# PowerSupply.net
KiCad netlist of a schematic drawn in Altium Designer
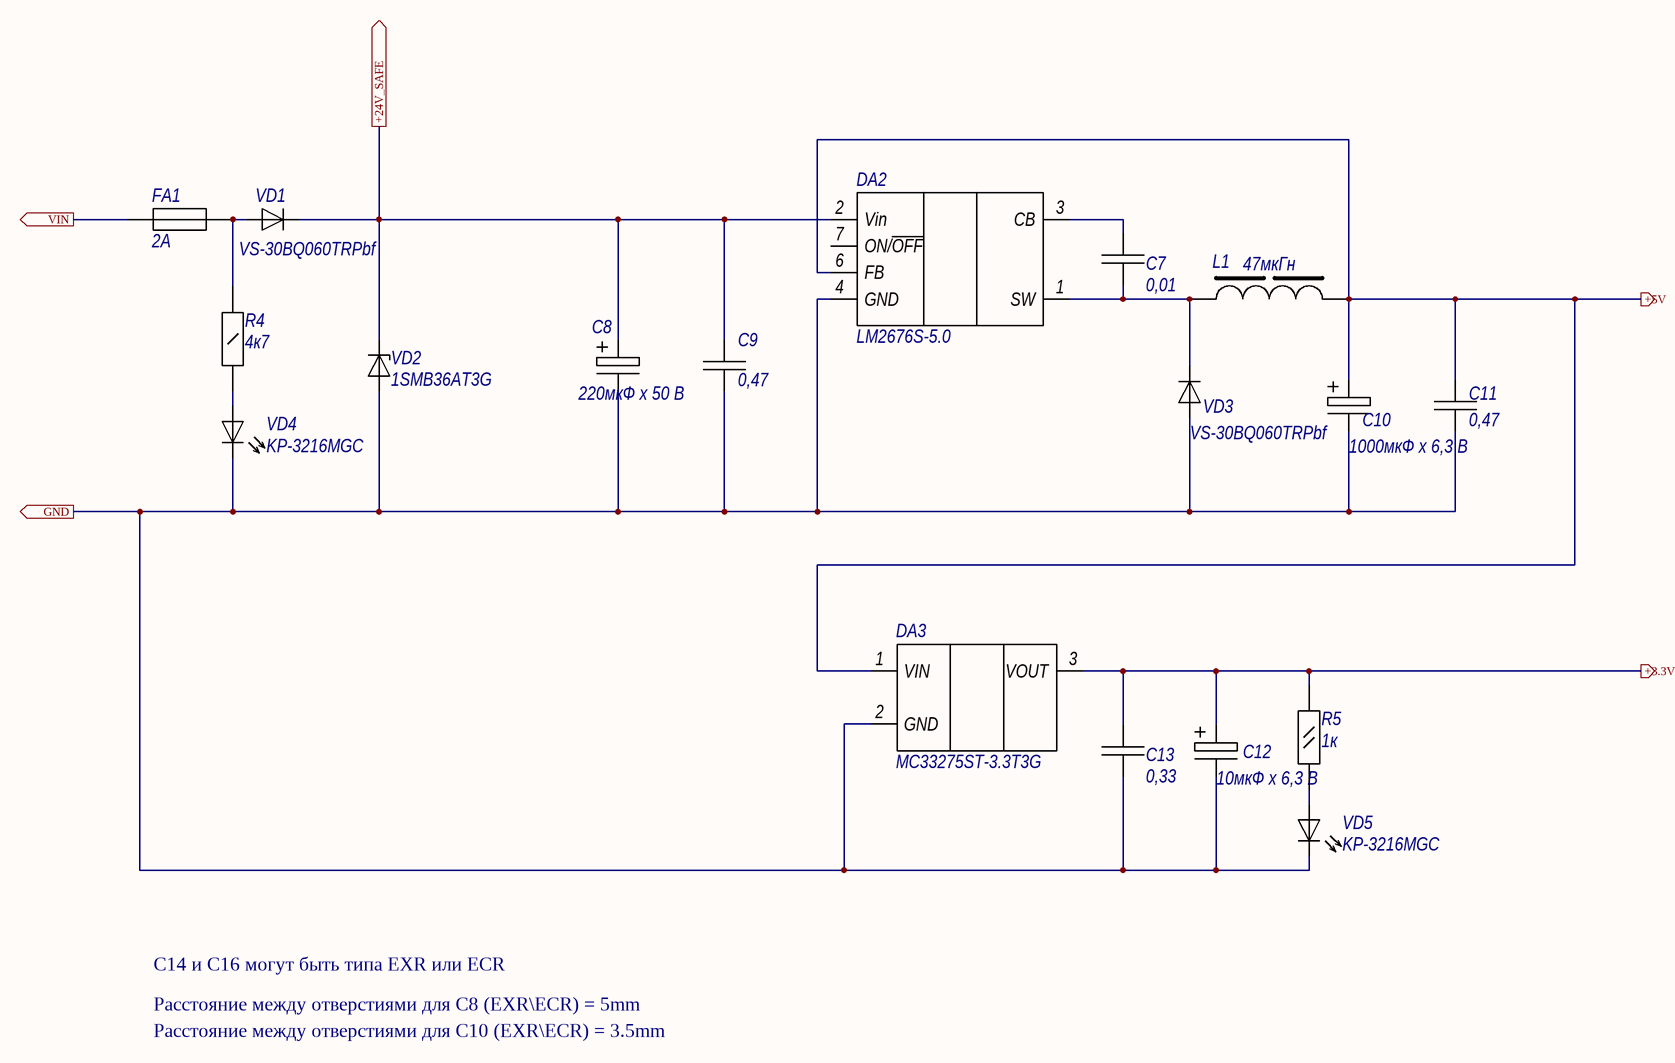
[diagram p0: PowerSupply.SchDoc]

(export (version "E")
  (design (tool "Eeschema 10.0.6"))
  (components
    (comp (ref "C7")
      (value "0,01")
      (footprint "0805")
      (description "Конденсатор")
      (fields (field (name "MANUFACTURER") "YAGEO"))
      (libsource (lib "DX_test_lib2") (part "CC0805"))
    )
    (comp (ref "C8")
      (value "220мкФ x 50 В")
      (footprint "ELCAP_SIZE_F")
      (description "Конденсатор электролитический")
      (fields (field (name "MANUFACTURER") "HITANO"))
      (libsource (lib "DX_test_lib2") (part "EZV-F"))
    )
    (comp (ref "C9")
      (value "0,47")
      (footprint "1206")
      (fields (field (name "MANUFACTURER") "YAGEO"))
      (libsource (lib "Capacitors") (part "CC1206"))
    )
    (comp (ref "C10")
      (value "1000мкФ x 6,3 В")
      (footprint "ELCAP_SIZE_F")
      (description "Конденсатор электролитический")
      (fields (field (name "MANUFACTURER") "HITANO"))
      (libsource (lib "DX_test_lib2") (part "EZV-F"))
    )
    (comp (ref "C11")
      (value "0,47")
      (footprint "1206")
      (fields (field (name "MANUFACTURER") "YAGEO"))
      (libsource (lib "Capacitors") (part "CC1206"))
    )
    (comp (ref "C12")
      (value "10мкФ x 6,3 В")
      (footprint "CAP_TYPE_A")
      (fields (field (name "MANUFACTURER") "Vishay"))
      (libsource (lib "Capacitors") (part "TANTAL_A"))
    )
    (comp (ref "C13")
      (value "0,33")
      (footprint "0805")
      (description "Конденсатор")
      (fields (field (name "MANUFACTURER") "YAGEO"))
      (libsource (lib "DX_test_lib2") (part "CC0805"))
    )
    (comp (ref "DA2")
      (value "LM2676S-5.0")
      (footprint "DDPAK")
      (description "понижающи регулятор 3 А")
      (fields (field (name "MANUFACTURER") "Texas Instr."))
      (libsource (lib "DX_test_lib2") (part "LM2676S"))
    )
    (comp (ref "DA3")
      (value "MC33275ST-3.3T3G")
      (footprint "SOT-223_2")
      (description "Линейный стабилизатор напряжения")
      (fields (field (name "MANUFACTURER") "ON Semi."))
      (libsource (lib "Micro_Analog") (part "MC33275ST"))
    )
    (comp (ref "FA1")
      (value "2А")
      (footprint "RUE-185")
      (description "Предохранитель 3,7 А 30 В")
      (fields (field (name "MANUFACTURER") "Tyco"))
      (libsource (lib "Miscellaneous") (part "RUE-185"))
    )
    (comp (ref "L1")
      (value "47мкГн")
      (footprint "B82464g4")
      (description "Силовой дроссель")
      (fields (field (name "MANUFACTURER") "Epcos"))
      (libsource (lib "DX_test_lib2") (part "B82464g4"))
    )
    (comp (ref "R4")
      (value "4к7")
      (footprint "1206")
      (description "Резистор общего назначения 5%")
      (fields (field (name "MANUFACTURER") "YAGEO"))
      (libsource (lib "Resistors") (part "RC1206JR"))
    )
    (comp (ref "R5")
      (value "1к")
      (footprint "0805")
      (description "Резистор общего назначения 5%")
      (fields (field (name "MANUFACTURER") "YAGEO"))
      (libsource (lib "DX_test_lib2") (part "RC0805JR"))
    )
    (comp (ref "VD1")
      (value "VS-30BQ060TRPbf")
      (footprint "SMC")
      (description "Диод Шотки 60 В 3 А")
      (fields (field (name "MANUFACTURER") "Vishay"))
      (libsource (lib "Diodes") (part "30BQ60"))
    )
    (comp (ref "VD2")
      (value "1SMB36AT3G")
      (footprint "SMB")
      (description "Диод защитный 600 Вт 36 В")
      (fields (field (name "MANUFACTURER") "On Semi."))
      (libsource (lib "Diodes") (part "1SMB36"))
    )
    (comp (ref "VD3")
      (value "VS-30BQ060TRPbf")
      (footprint "SMC")
      (description "Диод Шотки 60 В 3 А")
      (fields (field (name "MANUFACTURER") "Vishay"))
      (libsource (lib "Diodes") (part "30BQ60"))
    )
    (comp (ref "VD4")
      (value "KP-3216MGC")
      (footprint "LED3216")
      (description "Светодиод")
      (fields (field (name "MANUFACTURER") "Kingbright"))
      (libsource (lib "DX_test_lib2") (part "KP-3216"))
    )
    (comp (ref "VD5")
      (value "KP-3216MGC")
      (footprint "LED3216")
      (description "Светодиод")
      (fields (field (name "MANUFACTURER") "Kingbright"))
      (libsource (lib "DX_test_lib2") (part "KP-3216"))
    )
  )
  (nets
    (net (code "1") (name "/+3.3V") (class "Default")
      (node (ref "C12") (pin "1") (pinfunction "1_1") (pintype "passive"))
      (node (ref "C13") (pin "1") (pinfunction "1_1") (pintype "passive"))
      (node (ref "DA3") (pin "3") (pinfunction "VOUT_3") (pintype "passive"))
      (node (ref "R5") (pin "2") (pinfunction "2_2") (pintype "passive"))
    )
    (net (code "2") (name "/+5V") (class "Default")
      (node (ref "C10") (pin "1") (pinfunction "1_1") (pintype "passive"))
      (node (ref "C11") (pin "1") (pinfunction "1_1") (pintype "passive"))
      (node (ref "DA2") (pin "6") (pinfunction "FB_6") (pintype "passive"))
      (node (ref "DA3") (pin "1") (pinfunction "VIN_1") (pintype "passive"))
      (node (ref "L1") (pin "2") (pinfunction "2_2") (pintype "passive"))
    )
    (net (code "3") (name "/+24V_SAFE") (class "Default")
      (node (ref "C8") (pin "1") (pinfunction "1_1") (pintype "passive"))
      (node (ref "C9") (pin "1") (pinfunction "1_1") (pintype "passive"))
      (node (ref "DA2") (pin "2") (pinfunction "Vin_2") (pintype "passive"))
      (node (ref "VD1") (pin "1") (pinfunction "K_1") (pintype "passive"))
      (node (ref "VD2") (pin "1") (pinfunction "K_1") (pintype "passive"))
    )
    (net (code "4") (name "/GND") (class "Default")
      (node (ref "C10") (pin "2") (pinfunction "2_2") (pintype "passive"))
      (node (ref "C11") (pin "2") (pinfunction "2_2") (pintype "passive"))
      (node (ref "C12") (pin "2") (pinfunction "2_2") (pintype "passive"))
      (node (ref "C13") (pin "2") (pinfunction "2_2") (pintype "passive"))
      (node (ref "C8") (pin "2") (pinfunction "2_2") (pintype "passive"))
      (node (ref "C9") (pin "2") (pinfunction "2_2") (pintype "passive"))
      (node (ref "DA2") (pin "4") (pinfunction "GND_4") (pintype "passive"))
      (node (ref "DA3") (pin "2") (pinfunction "GND_2") (pintype "passive"))
      (node (ref "VD2") (pin "2") (pinfunction "A_2") (pintype "passive"))
      (node (ref "VD3") (pin "2") (pinfunction "A_2") (pintype "passive"))
      (node (ref "VD4") (pin "2") (pinfunction "K_2") (pintype "passive"))
      (node (ref "VD5") (pin "2") (pinfunction "K_2") (pintype "passive"))
    )
    (net (code "5") (name "/VIN") (class "Default")
      (node (ref "FA1") (pin "1") (pinfunction "1_1") (pintype "passive"))
    )
    (net (code "6") (name "Net-(DA2-CB)") (class "Default")
      (node (ref "C7") (pin "1") (pinfunction "1_1") (pintype "passive"))
      (node (ref "DA2") (pin "3") (pinfunction "CB_3") (pintype "passive"))
    )
    (net (code "7") (name "Net-(DA2-SW)") (class "Default")
      (node (ref "C7") (pin "2") (pinfunction "2_2") (pintype "passive"))
      (node (ref "DA2") (pin "1") (pinfunction "SW_1") (pintype "passive"))
      (node (ref "L1") (pin "1") (pinfunction "1_1") (pintype "passive"))
      (node (ref "VD3") (pin "1") (pinfunction "K_1") (pintype "passive"))
    )
    (net (code "8") (name "Net-(VD1-A)") (class "Default")
      (node (ref "FA1") (pin "2") (pinfunction "2_2") (pintype "passive"))
      (node (ref "R4") (pin "2") (pinfunction "2_2") (pintype "passive"))
      (node (ref "VD1") (pin "2") (pinfunction "A_2") (pintype "passive"))
    )
    (net (code "9") (name "Net-(VD4-A)") (class "Default")
      (node (ref "R4") (pin "1") (pinfunction "1_1") (pintype "passive"))
      (node (ref "VD4") (pin "1") (pinfunction "A_1") (pintype "passive"))
    )
    (net (code "10") (name "Net-(VD5-A)") (class "Default")
      (node (ref "R5") (pin "1") (pinfunction "1_1") (pintype "passive"))
      (node (ref "VD5") (pin "1") (pinfunction "A_1") (pintype "passive"))
    )
    (net (code "11") (name "unconnected-(DA2-ON{slash}~{OFF}-Pad7)") (class "Default")
      (node (ref "DA2") (pin "7") (pinfunction "ON/~{OFF}_7") (pintype "passive"))
    )
  )
)
